# haptic_hands.net
KiCad netlist of a schematic drawn in Altium Designer
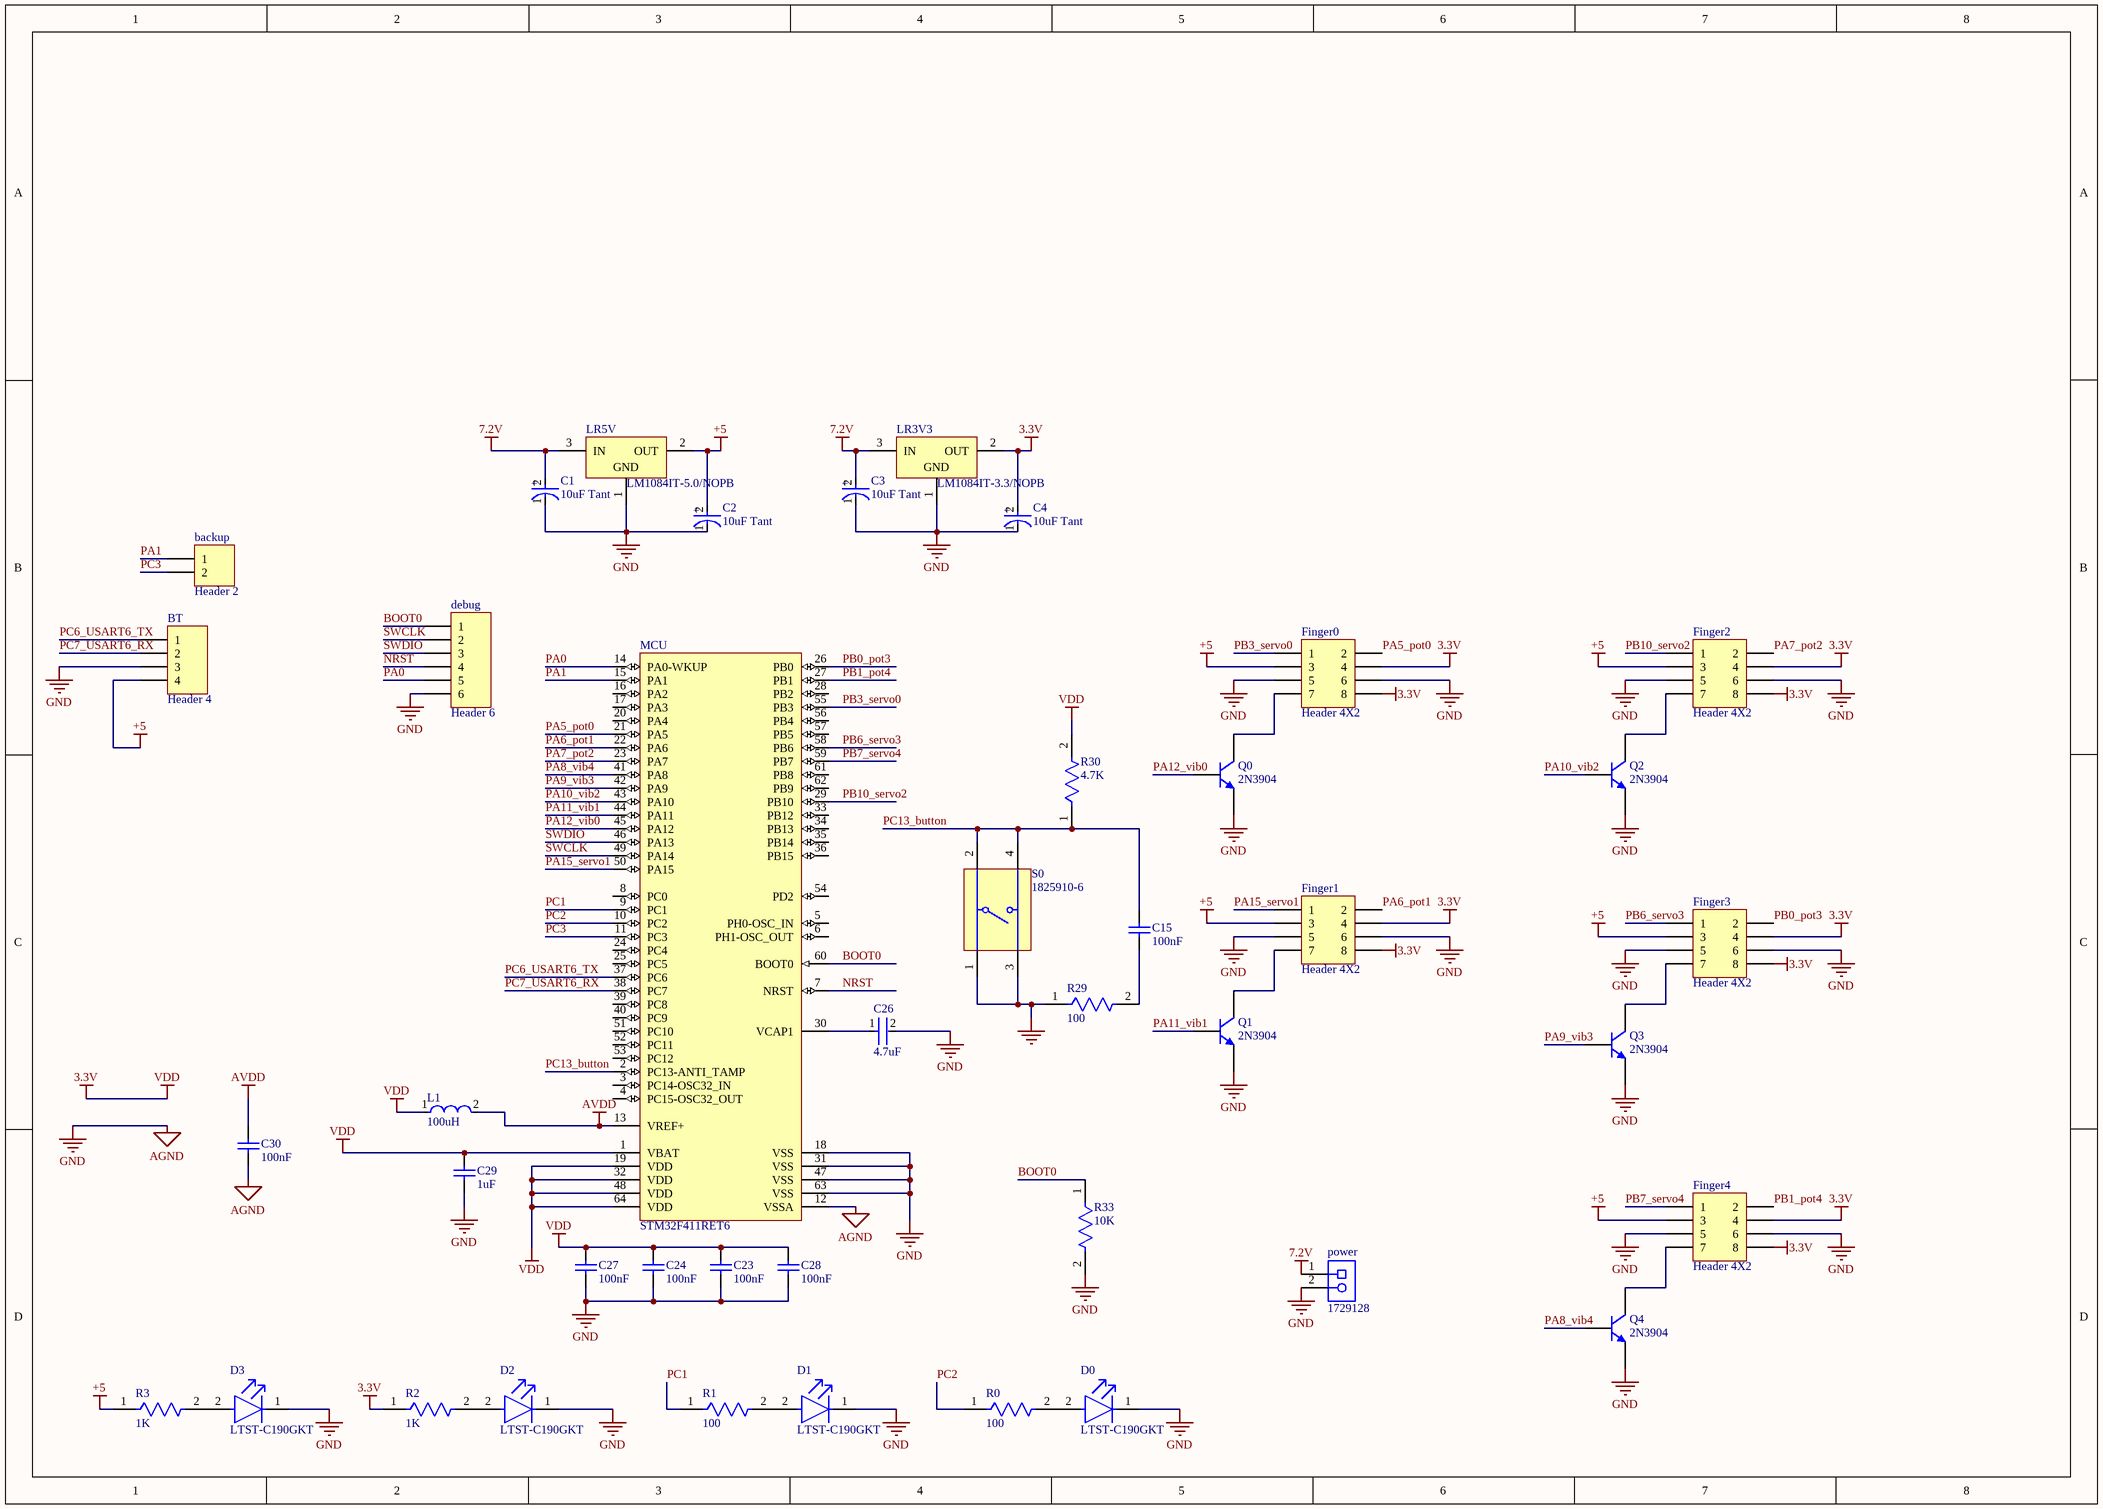
[diagram p0: haptic_hands.SchDoc]

(export (version "E")
  (design (tool "Eeschema 10.0.6"))
  (components
    (comp (ref "backup")
      (value "Header 2")
      (footprint "HDR1X2")
      (description "Header, 2-Pin")
      (fields (field (name "PUBLISHER") "Altium Limited"))
      (libsource (lib "Miscellaneous Connectors") (part "Header 2"))
    )
    (comp (ref "BT")
      (value "Header 4")
      (footprint "HDR1X4")
      (description "Header, 4-Pin")
      (fields (field (name "PUBLISHER") "Altium Limited"))
      (libsource (lib "Miscellaneous Connectors") (part "Header 4"))
    )
    (comp (ref "C1")
      (value "10uF Tant")
      (footprint "FP-T491A105K016AT-MFG")
      (description "10uF TANTALUM\r\nT494A106K016AT")
      (fields (field (name "TOLERANCE") "20%") (field (name "VOLTAGE") "16V"))
      (libsource (lib "Altium Content Vault") (part "203bc49f2ac43e59fd269a8c329ed05"))
    )
    (comp (ref "C2")
      (value "10uF Tant")
      (footprint "FP-T491A105K016AT-MFG")
      (description "10uF TANTALUM\r\nT494A106K016AT")
      (fields (field (name "TOLERANCE") "20%") (field (name "VOLTAGE") "16V"))
      (libsource (lib "Altium Content Vault") (part "203bc49f2ac43e59fd269a8c329ed05"))
    )
    (comp (ref "C3")
      (value "10uF Tant")
      (footprint "FP-T491A105K016AT-MFG")
      (description "10uF TANTALUM\r\nT494A106K016AT")
      (fields (field (name "TOLERANCE") "20%") (field (name "VOLTAGE") "16V"))
      (libsource (lib "Altium Content Vault") (part "203bc49f2ac43e59fd269a8c329ed05"))
    )
    (comp (ref "C4")
      (value "10uF Tant")
      (footprint "FP-T491A105K016AT-MFG")
      (description "10uF TANTALUM\r\nT494A106K016AT")
      (fields (field (name "TOLERANCE") "20%") (field (name "VOLTAGE") "16V"))
      (libsource (lib "Altium Content Vault") (part "203bc49f2ac43e59fd269a8c329ed05"))
    )
    (comp (ref "C15")
      (value "100nF")
      (footprint "CAPC1608X92X38NL15T08")
      (fields (field (name "MANUFACTURER") "Vitramon") (field (name "PART NUMBER") "VJ0603Y104KXAAC"))
      (libsource (lib "Altium Content Vault") (part "CAP"))
    )
    (comp (ref "C23")
      (value "100nF")
      (footprint "CAPC1608X92X38NL15T08")
      (fields (field (name "MANUFACTURER") "Vitramon") (field (name "PART NUMBER") "VJ0603Y104KXAAC"))
      (libsource (lib "Altium Content Vault") (part "CAP"))
    )
    (comp (ref "C24")
      (value "100nF")
      (footprint "CAPC1608X92X38NL15T08")
      (fields (field (name "MANUFACTURER") "Vitramon") (field (name "PART NUMBER") "VJ0603Y104KXAAC"))
      (libsource (lib "Altium Content Vault") (part "CAP"))
    )
    (comp (ref "C26")
      (value "4.7uF")
      (footprint "FP-GCJ31C-0_3-IPC_A")
      (description "Cap Ceramic 4.7uF 25V X7R 10% Pad SMD 1206 Soft Termination  +125°C Automotive T/R")
      (fields (field (name "TOLERANCE") "10%"))
      (libsource (lib "Altium Content Vault") (part "b4654b650e69147ec39a6b967a45e02"))
    )
    (comp (ref "C27")
      (value "100nF")
      (footprint "CAPC1608X92X38NL15T08")
      (fields (field (name "MANUFACTURER") "Vitramon") (field (name "PART NUMBER") "VJ0603Y104KXAAC"))
      (libsource (lib "Altium Content Vault") (part "CAP"))
    )
    (comp (ref "C28")
      (value "100nF")
      (footprint "CAPC1608X92X38NL15T08")
      (fields (field (name "MANUFACTURER") "Vitramon") (field (name "PART NUMBER") "VJ0603Y104KXAAC"))
      (libsource (lib "Altium Content Vault") (part "CAP"))
    )
    (comp (ref "C29")
      (value "1uF")
      (footprint "CAPC1005X56X25ML10T15")
      (fields
        (field (name "PART NUMBER") "0402YD105KAT2A")
        (field (name "MANUFACTURER") "AVX Interconnect / Elco")
      )
      (libsource (lib "Altium Content Vault") (part "CAP"))
    )
    (comp (ref "C30")
      (value "100nF")
      (footprint "CAPC1608X92X38NL15T08")
      (fields (field (name "MANUFACTURER") "Vitramon") (field (name "PART NUMBER") "VJ0603Y104KXAAC"))
      (libsource (lib "Altium Content Vault") (part "CAP"))
    )
    (comp (ref "D0")
      (value "LTST-C190GKT")
      (footprint "FP-LTST-C190GKT-MFG")
      (description "LED GREEN CLEAR CHIP SMD")
      (fields (field (name "VOLTAGE") "2V"))
      (libsource (lib "Altium Content Vault") (part "8706943c75ba83719d021d2fdc84c58"))
    )
    (comp (ref "D1")
      (value "LTST-C190GKT")
      (footprint "FP-LTST-C190GKT-MFG")
      (description "LED GREEN CLEAR CHIP SMD")
      (fields (field (name "VOLTAGE") "2V"))
      (libsource (lib "Altium Content Vault") (part "8706943c75ba83719d021d2fdc84c58"))
    )
    (comp (ref "D2")
      (value "LTST-C190GKT")
      (footprint "FP-LTST-C190GKT-MFG")
      (description "LED GREEN CLEAR CHIP SMD")
      (fields (field (name "VOLTAGE") "2V"))
      (libsource (lib "Altium Content Vault") (part "8706943c75ba83719d021d2fdc84c58"))
    )
    (comp (ref "D3")
      (value "LTST-C190GKT")
      (footprint "FP-LTST-C190GKT-MFG")
      (description "LED GREEN CLEAR CHIP SMD")
      (fields (field (name "VOLTAGE") "2V"))
      (libsource (lib "Altium Content Vault") (part "8706943c75ba83719d021d2fdc84c58"))
    )
    (comp (ref "debug")
      (value "Header 6")
      (footprint "HDR1X6")
      (description "Header, 6-Pin")
      (fields (field (name "PUBLISHER") "Altium Limited"))
      (libsource (lib "Miscellaneous Connectors") (part "Header 6"))
    )
    (comp (ref "Finger0")
      (value "Header 4X2")
      (footprint "HDR2X4")
      (description "Header, 4-Pin, Dual row")
      (fields (field (name "PUBLISHER") "Altium Limited"))
      (libsource (lib "Miscellaneous Connectors") (part "Header 4X2"))
    )
    (comp (ref "Finger1")
      (value "Header 4X2")
      (footprint "HDR2X4")
      (description "Header, 4-Pin, Dual row")
      (fields (field (name "PUBLISHER") "Altium Limited"))
      (libsource (lib "Miscellaneous Connectors") (part "Header 4X2"))
    )
    (comp (ref "Finger2")
      (value "Header 4X2")
      (footprint "HDR2X4")
      (description "Header, 4-Pin, Dual row")
      (fields (field (name "PUBLISHER") "Altium Limited"))
      (libsource (lib "Miscellaneous Connectors") (part "Header 4X2"))
    )
    (comp (ref "Finger3")
      (value "Header 4X2")
      (footprint "HDR2X4")
      (description "Header, 4-Pin, Dual row")
      (fields (field (name "PUBLISHER") "Altium Limited"))
      (libsource (lib "Miscellaneous Connectors") (part "Header 4X2"))
    )
    (comp (ref "Finger4")
      (value "Header 4X2")
      (footprint "HDR2X4")
      (description "Header, 4-Pin, Dual row")
      (fields (field (name "PUBLISHER") "Altium Limited"))
      (libsource (lib "Miscellaneous Connectors") (part "Header 4X2"))
    )
    (comp (ref "L1")
      (value "100uH")
      (footprint "FP-LBM2016-1_6-0_2-IPC_A")
      (description "SMD Inductors 100uH ±5% 0.08A 10.4Ω 0806")
      (libsource (lib "Altium Content Vault") (part "725321dda6339637d4d059423bc1c3c"))
    )
    (comp (ref "LR3V3")
      (value "LM1084IT-3.3/NOPB")
      (footprint "NDE0003A")
      (description "5A Low Dropout Positive Regulators, 3-pin TO-220, Pb-Free")
      (fields (field (name "MANUFACTURER") "Texas Instruments"))
      (libsource (lib "Altium Content Vault") (part "PM-REG-LM1086-SIL3"))
    )
    (comp (ref "LR5V")
      (value "LM1084IT-5.0/NOPB")
      (footprint "NDE0003A")
      (description "5A Low Dropout Positive Regulators, 3-pin TO-220, Pb-Free")
      (fields (field (name "MANUFACTURER") "Texas Instruments"))
      (libsource (lib "Altium Content Vault") (part "PM-REG-LM1086-SIL3"))
    )
    (comp (ref "MCU")
      (value "STM32F411RET6")
      (footprint "STM-LQFP64_L")
      (description "ARM Cortex-M4 32-bit MCU+FPU, 512 KB Flash, 128 KB RAM, 50 I/Os, 64-Pin LQFP, -40 to 85 degC, Tray")
      (libsource (lib "Altium Content Vault") (part "MC-ARM-STM32F411-LQFP64"))
    )
    (comp (ref "power")
      (value "1729128")
      (footprint "PHOE-1729128-2_V")
      (description "PCB Terminal Block, 13.5 A, 400 V, 2-Pin THD, RoHS, Bulk")
      (fields (field (name "MANUFACTURER") "Phoenix Contact"))
      (libsource (lib "Altium Content Vault") (part "CN-2P-F-R2"))
    )
    (comp (ref "Q0")
      (value "2N3904")
      (footprint "TO-92A")
      (description "NPN General Purpose Amplifier")
      (fields (field (name "PUBLISHER") "Altium Limited"))
      (libsource (lib "Miscellaneous Devices") (part "2N3904"))
    )
    (comp (ref "Q1")
      (value "2N3904")
      (footprint "TO-92A")
      (description "NPN General Purpose Amplifier")
      (fields (field (name "PUBLISHER") "Altium Limited"))
      (libsource (lib "Miscellaneous Devices") (part "2N3904"))
    )
    (comp (ref "Q2")
      (value "2N3904")
      (footprint "TO-92A")
      (description "NPN General Purpose Amplifier")
      (fields (field (name "PUBLISHER") "Altium Limited"))
      (libsource (lib "Miscellaneous Devices") (part "2N3904"))
    )
    (comp (ref "Q3")
      (value "2N3904")
      (footprint "TO-92A")
      (description "NPN General Purpose Amplifier")
      (fields (field (name "PUBLISHER") "Altium Limited"))
      (libsource (lib "Miscellaneous Devices") (part "2N3904"))
    )
    (comp (ref "Q4")
      (value "2N3904")
      (footprint "TO-92A")
      (description "NPN General Purpose Amplifier")
      (fields (field (name "PUBLISHER") "Altium Limited"))
      (libsource (lib "Miscellaneous Devices") (part "2N3904"))
    )
    (comp (ref "R0")
      (value "100")
      (footprint "FP-CR1206-IPC_A")
      (description "Thick Film Chip Resistors 1206 1kΩ 0.25W 1% 100ppm/°C")
      (fields (field (name "TOLERANCE") "1%"))
      (libsource (lib "Altium Content Vault") (part "1029c3af85768c4190bb7ad29bc67b5"))
    )
    (comp (ref "R1")
      (value "100")
      (footprint "FP-CR1206-IPC_A")
      (description "Thick Film Chip Resistors 1206 1kΩ 0.25W 1% 100ppm/°C")
      (fields (field (name "TOLERANCE") "1%"))
      (libsource (lib "Altium Content Vault") (part "1029c3af85768c4190bb7ad29bc67b5"))
    )
    (comp (ref "R2")
      (value "1K")
      (footprint "FP-CR1206-IPC_A")
      (description "Thick Film Chip Resistors 1206 1kΩ 0.25W 1% 100ppm/°C")
      (fields (field (name "TOLERANCE") "1%"))
      (libsource (lib "Altium Content Vault") (part "1029c3af85768c4190bb7ad29bc67b5"))
    )
    (comp (ref "R3")
      (value "1K")
      (footprint "FP-CR1206-IPC_A")
      (description "Thick Film Chip Resistors 1206 1kΩ 0.25W 1% 100ppm/°C")
      (fields (field (name "TOLERANCE") "1%"))
      (libsource (lib "Altium Content Vault") (part "1029c3af85768c4190bb7ad29bc67b5"))
    )
    (comp (ref "R29")
      (value "100")
      (footprint "FP-CR1206-IPC_A")
      (description "Thick Film Chip Resistors 1206 1kΩ 0.25W 1% 100ppm/°C")
      (fields (field (name "TOLERANCE") "1%"))
      (libsource (lib "Altium Content Vault") (part "1029c3af85768c4190bb7ad29bc67b5"))
    )
    (comp (ref "R30")
      (value "4.7K")
      (footprint "FP-CR1206-IPC_A")
      (description "Thick Film Chip Resistors 1206 1kΩ 0.25W 1% 100ppm/°C")
      (fields (field (name "TOLERANCE") "1%"))
      (libsource (lib "Altium Content Vault") (part "1029c3af85768c4190bb7ad29bc67b5"))
    )
    (comp (ref "R33")
      (value "10K")
      (footprint "FP-CR1206-IPC_A")
      (description "Thick Film Chip Resistors 1206 1kΩ 0.25W 1% 100ppm/°C")
      (fields (field (name "TOLERANCE") "1%"))
      (libsource (lib "Altium Content Vault") (part "1029c3af85768c4190bb7ad29bc67b5"))
    )
    (comp (ref "S0")
      (value "1825910-6")
      (footprint "TECO-1825910-6_V")
      (description "Tact Switch, SPST-NO, 0.05 A, -35 to 85 degC, 4-Pin THD, RoHS, Bulk")
      (fields (field (name "MANUFACTURER") "TE Connectivity"))
      (libsource (lib "Altium Content Vault") (part "SW-SPST-4_A"))
    )
  )
  (nets
    (net (code "1") (name "+5") (class "Default")
      (node (ref "BT") (pin "4") (pinfunction "4_4") (pintype "passive"))
      (node (ref "C2") (pin "2") (pinfunction "A_2") (pintype "passive"))
      (node (ref "Finger0") (pin "3") (pinfunction "3_3") (pintype "passive"))
      (node (ref "Finger1") (pin "3") (pinfunction "3_3") (pintype "passive"))
      (node (ref "Finger2") (pin "3") (pinfunction "3_3") (pintype "passive"))
      (node (ref "Finger3") (pin "3") (pinfunction "3_3") (pintype "passive"))
      (node (ref "Finger4") (pin "3") (pinfunction "3_3") (pintype "passive"))
      (node (ref "LR5V") (pin "2") (pinfunction "OUT_2") (pintype "power_in"))
      (node (ref "R3") (pin "1") (pinfunction "1_1") (pintype "passive"))
    )
    (net (code "2") (name "/BOOT0") (class "Default")
      (node (ref "MCU") (pin "60") (pinfunction "BOOT0_60") (pintype "input"))
      (node (ref "R33") (pin "1") (pinfunction "1_1") (pintype "passive"))
      (node (ref "debug") (pin "1") (pinfunction "1_1") (pintype "passive"))
    )
    (net (code "3") (name "/NRST") (class "Default")
      (node (ref "MCU") (pin "7") (pinfunction "NRST_7") (pintype "bidirectional"))
      (node (ref "debug") (pin "4") (pinfunction "4_4") (pintype "passive"))
    )
    (net (code "4") (name "/PA0") (class "Default")
      (node (ref "MCU") (pin "14") (pinfunction "PA0-WKUP_14") (pintype "bidirectional"))
      (node (ref "debug") (pin "5") (pinfunction "5_5") (pintype "passive"))
    )
    (net (code "5") (name "/PA1") (class "Default")
      (node (ref "MCU") (pin "15") (pinfunction "PA1_15") (pintype "bidirectional"))
      (node (ref "backup") (pin "1") (pinfunction "1_1") (pintype "passive"))
    )
    (net (code "6") (name "/PA5_pot0") (class "Default")
      (node (ref "Finger0") (pin "2") (pinfunction "2_2") (pintype "passive"))
      (node (ref "MCU") (pin "21") (pinfunction "PA5_21") (pintype "bidirectional"))
    )
    (net (code "7") (name "/PA6_pot1") (class "Default")
      (node (ref "Finger1") (pin "2") (pinfunction "2_2") (pintype "passive"))
      (node (ref "MCU") (pin "22") (pinfunction "PA6_22") (pintype "bidirectional"))
    )
    (net (code "8") (name "/PA7_pot2") (class "Default")
      (node (ref "Finger2") (pin "2") (pinfunction "2_2") (pintype "passive"))
      (node (ref "MCU") (pin "23") (pinfunction "PA7_23") (pintype "bidirectional"))
    )
    (net (code "9") (name "/PA8_vib4") (class "Default")
      (node (ref "MCU") (pin "41") (pinfunction "PA8_41") (pintype "bidirectional"))
      (node (ref "Q4") (pin "2") (pinfunction "B_2") (pintype "passive"))
    )
    (net (code "10") (name "/PA9_vib3") (class "Default")
      (node (ref "MCU") (pin "42") (pinfunction "PA9_42") (pintype "bidirectional"))
      (node (ref "Q3") (pin "2") (pinfunction "B_2") (pintype "passive"))
    )
    (net (code "11") (name "/PA10_vib2") (class "Default")
      (node (ref "MCU") (pin "43") (pinfunction "PA10_43") (pintype "bidirectional"))
      (node (ref "Q2") (pin "2") (pinfunction "B_2") (pintype "passive"))
    )
    (net (code "12") (name "/PA11_vib1") (class "Default")
      (node (ref "MCU") (pin "44") (pinfunction "PA11_44") (pintype "bidirectional"))
      (node (ref "Q1") (pin "2") (pinfunction "B_2") (pintype "passive"))
    )
    (net (code "13") (name "/PA12_vib0") (class "Default")
      (node (ref "MCU") (pin "45") (pinfunction "PA12_45") (pintype "bidirectional"))
      (node (ref "Q0") (pin "2") (pinfunction "B_2") (pintype "passive"))
    )
    (net (code "14") (name "/PA15_servo1") (class "Default")
      (node (ref "Finger1") (pin "1") (pinfunction "1_1") (pintype "passive"))
      (node (ref "MCU") (pin "50") (pinfunction "PA15_50") (pintype "bidirectional"))
    )
    (net (code "15") (name "/PB0_pot3") (class "Default")
      (node (ref "Finger3") (pin "2") (pinfunction "2_2") (pintype "passive"))
      (node (ref "MCU") (pin "26") (pinfunction "PB0_26") (pintype "bidirectional"))
    )
    (net (code "16") (name "/PB1_pot4") (class "Default")
      (node (ref "Finger4") (pin "2") (pinfunction "2_2") (pintype "passive"))
      (node (ref "MCU") (pin "27") (pinfunction "PB1_27") (pintype "bidirectional"))
    )
    (net (code "17") (name "/PB3_servo0") (class "Default")
      (node (ref "Finger0") (pin "1") (pinfunction "1_1") (pintype "passive"))
      (node (ref "MCU") (pin "55") (pinfunction "PB3_55") (pintype "bidirectional"))
    )
    (net (code "18") (name "/PB6_servo3") (class "Default")
      (node (ref "Finger3") (pin "1") (pinfunction "1_1") (pintype "passive"))
      (node (ref "MCU") (pin "58") (pinfunction "PB6_58") (pintype "bidirectional"))
    )
    (net (code "19") (name "/PB7_servo4") (class "Default")
      (node (ref "Finger4") (pin "1") (pinfunction "1_1") (pintype "passive"))
      (node (ref "MCU") (pin "59") (pinfunction "PB7_59") (pintype "bidirectional"))
    )
    (net (code "20") (name "/PB10_servo2") (class "Default")
      (node (ref "Finger2") (pin "1") (pinfunction "1_1") (pintype "passive"))
      (node (ref "MCU") (pin "29") (pinfunction "PB10_29") (pintype "bidirectional"))
    )
    (net (code "21") (name "/PC1") (class "Default")
      (node (ref "MCU") (pin "9") (pinfunction "PC1_9") (pintype "bidirectional"))
      (node (ref "R1") (pin "1") (pinfunction "1_1") (pintype "passive"))
    )
    (net (code "22") (name "/PC2") (class "Default")
      (node (ref "MCU") (pin "10") (pinfunction "PC2_10") (pintype "bidirectional"))
      (node (ref "R0") (pin "1") (pinfunction "1_1") (pintype "passive"))
    )
    (net (code "23") (name "/PC3") (class "Default")
      (node (ref "MCU") (pin "11") (pinfunction "PC3_11") (pintype "bidirectional"))
      (node (ref "backup") (pin "2") (pinfunction "2_2") (pintype "passive"))
    )
    (net (code "24") (name "/PC6_USART6_TX") (class "Default")
      (node (ref "BT") (pin "1") (pinfunction "1_1") (pintype "passive"))
      (node (ref "MCU") (pin "37") (pinfunction "PC6_37") (pintype "bidirectional"))
    )
    (net (code "25") (name "/PC7_USART6_RX") (class "Default")
      (node (ref "BT") (pin "2") (pinfunction "2_2") (pintype "passive"))
      (node (ref "MCU") (pin "38") (pinfunction "PC7_38") (pintype "bidirectional"))
    )
    (net (code "26") (name "/PC13_button") (class "Default")
      (node (ref "C15") (pin "2") (pinfunction "2_2") (pintype "passive"))
      (node (ref "MCU") (pin "2") (pinfunction "PC13-ANTI_TAMP_2") (pintype "bidirectional"))
      (node (ref "R30") (pin "1") (pinfunction "1_1") (pintype "passive"))
      (node (ref "S0") (pin "2") (pinfunction "2_2") (pintype "passive"))
      (node (ref "S0") (pin "4") (pinfunction "4_4") (pintype "passive"))
    )
    (net (code "27") (name "/SWCLK") (class "Default")
      (node (ref "MCU") (pin "49") (pinfunction "PA14_49") (pintype "bidirectional"))
      (node (ref "debug") (pin "2") (pinfunction "2_2") (pintype "passive"))
    )
    (net (code "28") (name "/SWDIO") (class "Default")
      (node (ref "MCU") (pin "46") (pinfunction "PA13_46") (pintype "bidirectional"))
      (node (ref "debug") (pin "3") (pinfunction "3_3") (pintype "passive"))
    )
    (net (code "29") (name "3.3V") (class "Default")
      (node (ref "C23") (pin "2") (pinfunction "2_2") (pintype "passive"))
      (node (ref "C24") (pin "2") (pinfunction "2_2") (pintype "passive"))
      (node (ref "C27") (pin "2") (pinfunction "2_2") (pintype "passive"))
      (node (ref "C28") (pin "2") (pinfunction "2_2") (pintype "passive"))
      (node (ref "C29") (pin "2") (pinfunction "2_2") (pintype "passive"))
      (node (ref "C4") (pin "2") (pinfunction "A_2") (pintype "passive"))
      (node (ref "Finger0") (pin "4") (pinfunction "4_4") (pintype "passive"))
      (node (ref "Finger0") (pin "8") (pinfunction "8_8") (pintype "passive"))
      (node (ref "Finger1") (pin "4") (pinfunction "4_4") (pintype "passive"))
      (node (ref "Finger1") (pin "8") (pinfunction "8_8") (pintype "passive"))
      (node (ref "Finger2") (pin "4") (pinfunction "4_4") (pintype "passive"))
      (node (ref "Finger2") (pin "8") (pinfunction "8_8") (pintype "passive"))
      (node (ref "Finger3") (pin "4") (pinfunction "4_4") (pintype "passive"))
      (node (ref "Finger3") (pin "8") (pinfunction "8_8") (pintype "passive"))
      (node (ref "Finger4") (pin "4") (pinfunction "4_4") (pintype "passive"))
      (node (ref "Finger4") (pin "8") (pinfunction "8_8") (pintype "passive"))
      (node (ref "L1") (pin "1") (pinfunction "1_1") (pintype "passive"))
      (node (ref "LR3V3") (pin "2") (pinfunction "OUT_2") (pintype "power_in"))
      (node (ref "MCU") (pin "1") (pinfunction "VBAT_1") (pintype "power_in"))
      (node (ref "MCU") (pin "19") (pinfunction "VDD_19") (pintype "power_in"))
      (node (ref "MCU") (pin "32") (pinfunction "VDD_32") (pintype "power_in"))
      (node (ref "MCU") (pin "48") (pinfunction "VDD_48") (pintype "power_in"))
      (node (ref "MCU") (pin "64") (pinfunction "VDD_64") (pintype "power_in"))
      (node (ref "R2") (pin "1") (pinfunction "1_1") (pintype "passive"))
      (node (ref "R30") (pin "2") (pinfunction "2_2") (pintype "passive"))
    )
    (net (code "30") (name "7.2V") (class "Default")
      (node (ref "C1") (pin "2") (pinfunction "A_2") (pintype "passive"))
      (node (ref "C3") (pin "2") (pinfunction "A_2") (pintype "passive"))
      (node (ref "LR3V3") (pin "3") (pinfunction "IN_3") (pintype "power_in"))
      (node (ref "LR5V") (pin "3") (pinfunction "IN_3") (pintype "power_in"))
      (node (ref "power") (pin "1") (pinfunction "1_1") (pintype "passive"))
    )
    (net (code "31") (name "AGND") (class "Default")
      (node (ref "BT") (pin "3") (pinfunction "3_3") (pintype "passive"))
      (node (ref "C1") (pin "1") (pinfunction "C_1") (pintype "passive"))
      (node (ref "C2") (pin "1") (pinfunction "C_1") (pintype "passive"))
      (node (ref "C23") (pin "1") (pinfunction "1_1") (pintype "passive"))
      (node (ref "C24") (pin "1") (pinfunction "1_1") (pintype "passive"))
      (node (ref "C26") (pin "2") (pinfunction "2_2") (pintype "passive"))
      (node (ref "C27") (pin "1") (pinfunction "1_1") (pintype "passive"))
      (node (ref "C28") (pin "1") (pinfunction "1_1") (pintype "passive"))
      (node (ref "C29") (pin "1") (pinfunction "1_1") (pintype "passive"))
      (node (ref "C3") (pin "1") (pinfunction "C_1") (pintype "passive"))
      (node (ref "C30") (pin "1") (pinfunction "1_1") (pintype "passive"))
      (node (ref "C4") (pin "1") (pinfunction "C_1") (pintype "passive"))
      (node (ref "D0") (pin "1") (pinfunction "C_1") (pintype "passive"))
      (node (ref "D1") (pin "1") (pinfunction "C_1") (pintype "passive"))
      (node (ref "D2") (pin "1") (pinfunction "C_1") (pintype "passive"))
      (node (ref "D3") (pin "1") (pinfunction "C_1") (pintype "passive"))
      (node (ref "Finger0") (pin "5") (pinfunction "5_5") (pintype "passive"))
      (node (ref "Finger0") (pin "6") (pinfunction "6_6") (pintype "passive"))
      (node (ref "Finger1") (pin "5") (pinfunction "5_5") (pintype "passive"))
      (node (ref "Finger1") (pin "6") (pinfunction "6_6") (pintype "passive"))
      (node (ref "Finger2") (pin "5") (pinfunction "5_5") (pintype "passive"))
      (node (ref "Finger2") (pin "6") (pinfunction "6_6") (pintype "passive"))
      (node (ref "Finger3") (pin "5") (pinfunction "5_5") (pintype "passive"))
      (node (ref "Finger3") (pin "6") (pinfunction "6_6") (pintype "passive"))
      (node (ref "Finger4") (pin "5") (pinfunction "5_5") (pintype "passive"))
      (node (ref "Finger4") (pin "6") (pinfunction "6_6") (pintype "passive"))
      (node (ref "LR3V3") (pin "1") (pinfunction "GND_1") (pintype "power_in"))
      (node (ref "LR5V") (pin "1") (pinfunction "GND_1") (pintype "power_in"))
      (node (ref "MCU") (pin "12") (pinfunction "VSSA_12") (pintype "power_in"))
      (node (ref "MCU") (pin "18") (pinfunction "VSS_18") (pintype "power_in"))
      (node (ref "MCU") (pin "31") (pinfunction "VSS_31") (pintype "power_in"))
      (node (ref "MCU") (pin "47") (pinfunction "VSS_47") (pintype "power_in"))
      (node (ref "MCU") (pin "63") (pinfunction "VSS_63") (pintype "power_in"))
      (node (ref "Q0") (pin "1") (pinfunction "E_1") (pintype "passive"))
      (node (ref "Q1") (pin "1") (pinfunction "E_1") (pintype "passive"))
      (node (ref "Q2") (pin "1") (pinfunction "E_1") (pintype "passive"))
      (node (ref "Q3") (pin "1") (pinfunction "E_1") (pintype "passive"))
      (node (ref "Q4") (pin "1") (pinfunction "E_1") (pintype "passive"))
      (node (ref "R29") (pin "1") (pinfunction "1_1") (pintype "passive"))
      (node (ref "R33") (pin "2") (pinfunction "2_2") (pintype "passive"))
      (node (ref "S0") (pin "1") (pinfunction "1_1") (pintype "passive"))
      (node (ref "S0") (pin "3") (pinfunction "3_3") (pintype "passive"))
      (node (ref "debug") (pin "6") (pinfunction "6_6") (pintype "passive"))
      (node (ref "power") (pin "2") (pinfunction "2_2") (pintype "passive"))
    )
    (net (code "32") (name "AVDD") (class "Default")
      (node (ref "C30") (pin "2") (pinfunction "2_2") (pintype "passive"))
      (node (ref "L1") (pin "2") (pinfunction "2_2") (pintype "passive"))
      (node (ref "MCU") (pin "13") (pinfunction "VREF+_13") (pintype "power_in"))
    )
    (net (code "33") (name "Net-(C15-Pad1)") (class "Default")
      (node (ref "C15") (pin "1") (pinfunction "1_1") (pintype "passive"))
      (node (ref "R29") (pin "2") (pinfunction "2_2") (pintype "passive"))
    )
    (net (code "34") (name "Net-(D0-A)") (class "Default")
      (node (ref "D0") (pin "2") (pinfunction "A_2") (pintype "passive"))
      (node (ref "R0") (pin "2") (pinfunction "2_2") (pintype "passive"))
    )
    (net (code "35") (name "Net-(D1-A)") (class "Default")
      (node (ref "D1") (pin "2") (pinfunction "A_2") (pintype "passive"))
      (node (ref "R1") (pin "2") (pinfunction "2_2") (pintype "passive"))
    )
    (net (code "36") (name "Net-(D2-A)") (class "Default")
      (node (ref "D2") (pin "2") (pinfunction "A_2") (pintype "passive"))
      (node (ref "R2") (pin "2") (pinfunction "2_2") (pintype "passive"))
    )
    (net (code "37") (name "Net-(D3-A)") (class "Default")
      (node (ref "D3") (pin "2") (pinfunction "A_2") (pintype "passive"))
      (node (ref "R3") (pin "2") (pinfunction "2_2") (pintype "passive"))
    )
    (net (code "38") (name "Net-(MCU-VCAP1)") (class "Default")
      (node (ref "C26") (pin "1") (pinfunction "1_1") (pintype "passive"))
      (node (ref "MCU") (pin "30") (pinfunction "VCAP1_30") (pintype "passive"))
    )
    (net (code "39") (name "Net-(Q0-C)") (class "Default")
      (node (ref "Finger0") (pin "7") (pinfunction "7_7") (pintype "passive"))
      (node (ref "Q0") (pin "3") (pinfunction "C_3") (pintype "passive"))
    )
    (net (code "40") (name "Net-(Q1-C)") (class "Default")
      (node (ref "Finger1") (pin "7") (pinfunction "7_7") (pintype "passive"))
      (node (ref "Q1") (pin "3") (pinfunction "C_3") (pintype "passive"))
    )
    (net (code "41") (name "Net-(Q2-C)") (class "Default")
      (node (ref "Finger2") (pin "7") (pinfunction "7_7") (pintype "passive"))
      (node (ref "Q2") (pin "3") (pinfunction "C_3") (pintype "passive"))
    )
    (net (code "42") (name "Net-(Q3-C)") (class "Default")
      (node (ref "Finger3") (pin "7") (pinfunction "7_7") (pintype "passive"))
      (node (ref "Q3") (pin "3") (pinfunction "C_3") (pintype "passive"))
    )
    (net (code "43") (name "Net-(Q4-C)") (class "Default")
      (node (ref "Finger4") (pin "7") (pinfunction "7_7") (pintype "passive"))
      (node (ref "Q4") (pin "3") (pinfunction "C_3") (pintype "passive"))
    )
    (net (code "44") (name "unconnected-(MCU-PA2-Pad16)") (class "Default")
      (node (ref "MCU") (pin "16") (pinfunction "PA2_16") (pintype "bidirectional"))
    )
    (net (code "45") (name "unconnected-(MCU-PA3-Pad17)") (class "Default")
      (node (ref "MCU") (pin "17") (pinfunction "PA3_17") (pintype "bidirectional"))
    )
    (net (code "46") (name "unconnected-(MCU-PA4-Pad20)") (class "Default")
      (node (ref "MCU") (pin "20") (pinfunction "PA4_20") (pintype "bidirectional"))
    )
    (net (code "47") (name "unconnected-(MCU-PB2-Pad28)") (class "Default")
      (node (ref "MCU") (pin "28") (pinfunction "PB2_28") (pintype "bidirectional"))
    )
    (net (code "48") (name "unconnected-(MCU-PB4-Pad56)") (class "Default")
      (node (ref "MCU") (pin "56") (pinfunction "PB4_56") (pintype "bidirectional"))
    )
    (net (code "49") (name "unconnected-(MCU-PB5-Pad57)") (class "Default")
      (node (ref "MCU") (pin "57") (pinfunction "PB5_57") (pintype "bidirectional"))
    )
    (net (code "50") (name "unconnected-(MCU-PB8-Pad61)") (class "Default")
      (node (ref "MCU") (pin "61") (pinfunction "PB8_61") (pintype "bidirectional"))
    )
    (net (code "51") (name "unconnected-(MCU-PB9-Pad62)") (class "Default")
      (node (ref "MCU") (pin "62") (pinfunction "PB9_62") (pintype "bidirectional"))
    )
    (net (code "52") (name "unconnected-(MCU-PB12-Pad33)") (class "Default")
      (node (ref "MCU") (pin "33") (pinfunction "PB12_33") (pintype "bidirectional"))
    )
    (net (code "53") (name "unconnected-(MCU-PB13-Pad34)") (class "Default")
      (node (ref "MCU") (pin "34") (pinfunction "PB13_34") (pintype "bidirectional"))
    )
    (net (code "54") (name "unconnected-(MCU-PB14-Pad35)") (class "Default")
      (node (ref "MCU") (pin "35") (pinfunction "PB14_35") (pintype "bidirectional"))
    )
    (net (code "55") (name "unconnected-(MCU-PB15-Pad36)") (class "Default")
      (node (ref "MCU") (pin "36") (pinfunction "PB15_36") (pintype "bidirectional"))
    )
    (net (code "56") (name "unconnected-(MCU-PC0-Pad8)") (class "Default")
      (node (ref "MCU") (pin "8") (pinfunction "PC0_8") (pintype "bidirectional"))
    )
    (net (code "57") (name "unconnected-(MCU-PC4-Pad24)") (class "Default")
      (node (ref "MCU") (pin "24") (pinfunction "PC4_24") (pintype "bidirectional"))
    )
    (net (code "58") (name "unconnected-(MCU-PC5-Pad25)") (class "Default")
      (node (ref "MCU") (pin "25") (pinfunction "PC5_25") (pintype "bidirectional"))
    )
    (net (code "59") (name "unconnected-(MCU-PC8-Pad39)") (class "Default")
      (node (ref "MCU") (pin "39") (pinfunction "PC8_39") (pintype "bidirectional"))
    )
    (net (code "60") (name "unconnected-(MCU-PC9-Pad40)") (class "Default")
      (node (ref "MCU") (pin "40") (pinfunction "PC9_40") (pintype "bidirectional"))
    )
    (net (code "61") (name "unconnected-(MCU-PC10-Pad51)") (class "Default")
      (node (ref "MCU") (pin "51") (pinfunction "PC10_51") (pintype "bidirectional"))
    )
    (net (code "62") (name "unconnected-(MCU-PC11-Pad52)") (class "Default")
      (node (ref "MCU") (pin "52") (pinfunction "PC11_52") (pintype "bidirectional"))
    )
    (net (code "63") (name "unconnected-(MCU-PC12-Pad53)") (class "Default")
      (node (ref "MCU") (pin "53") (pinfunction "PC12_53") (pintype "bidirectional"))
    )
    (net (code "64") (name "unconnected-(MCU-PC14-OSC32_IN-Pad3)") (class "Default")
      (node (ref "MCU") (pin "3") (pinfunction "PC14-OSC32_IN_3") (pintype "bidirectional"))
    )
    (net (code "65") (name "unconnected-(MCU-PC15-OSC32_OUT-Pad4)") (class "Default")
      (node (ref "MCU") (pin "4") (pinfunction "PC15-OSC32_OUT_4") (pintype "bidirectional"))
    )
    (net (code "66") (name "unconnected-(MCU-PD2-Pad54)") (class "Default")
      (node (ref "MCU") (pin "54") (pinfunction "PD2_54") (pintype "bidirectional"))
    )
    (net (code "67") (name "unconnected-(MCU-PH0-OSC_IN-Pad5)") (class "Default")
      (node (ref "MCU") (pin "5") (pinfunction "PH0-OSC_IN_5") (pintype "bidirectional"))
    )
    (net (code "68") (name "unconnected-(MCU-PH1-OSC_OUT-Pad6)") (class "Default")
      (node (ref "MCU") (pin "6") (pinfunction "PH1-OSC_OUT_6") (pintype "bidirectional"))
    )
  )
)
